# SenseBox-MCU-2-2.net
KiCad netlist of a schematic drawn in EAGLE
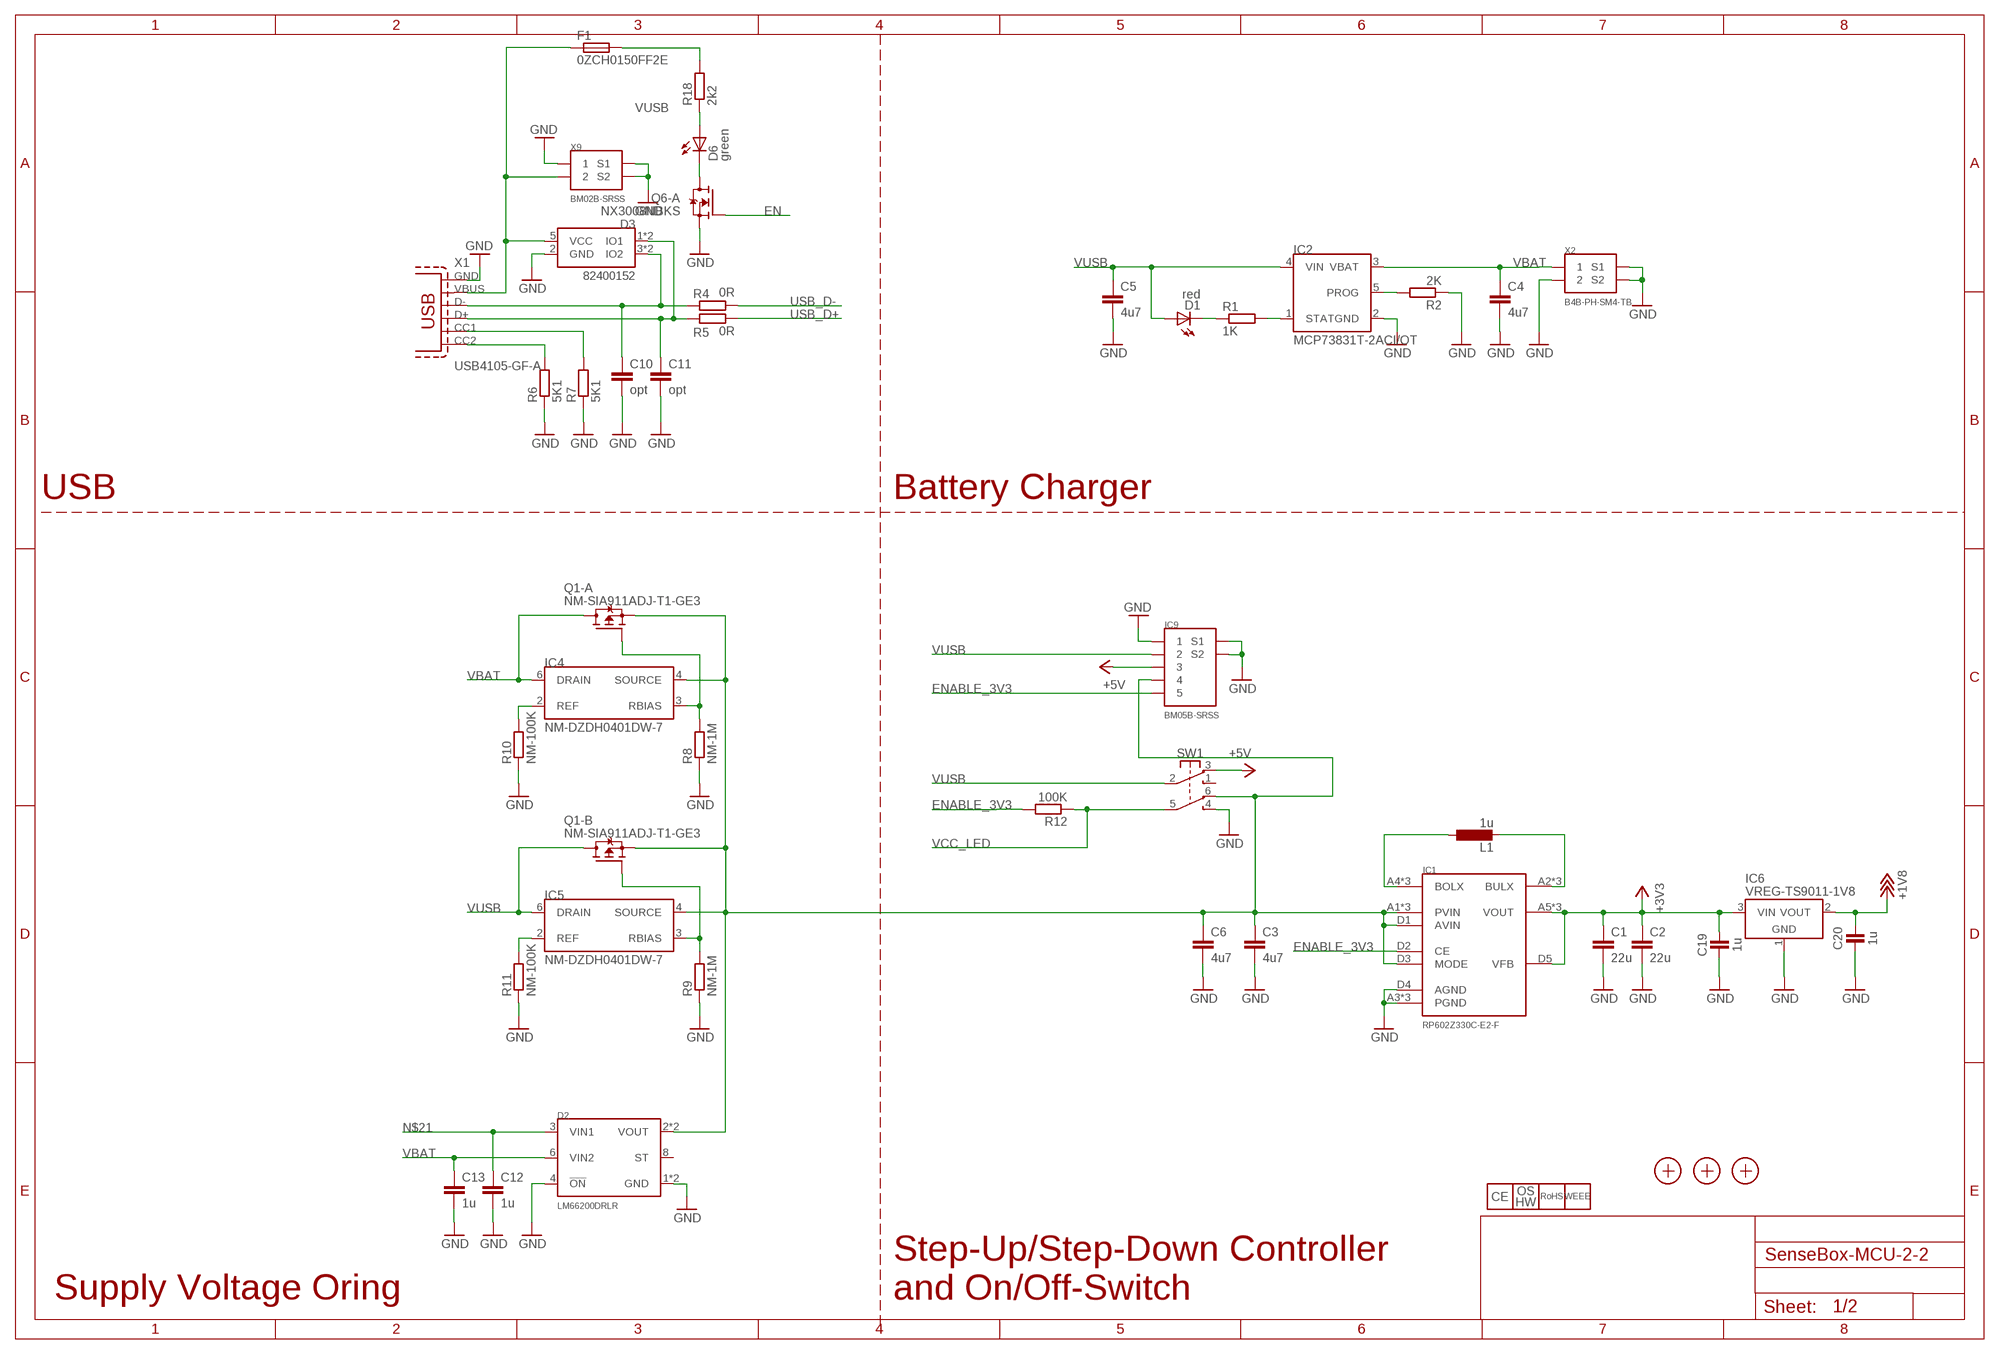
[diagram p0: schematic, sheet 1]
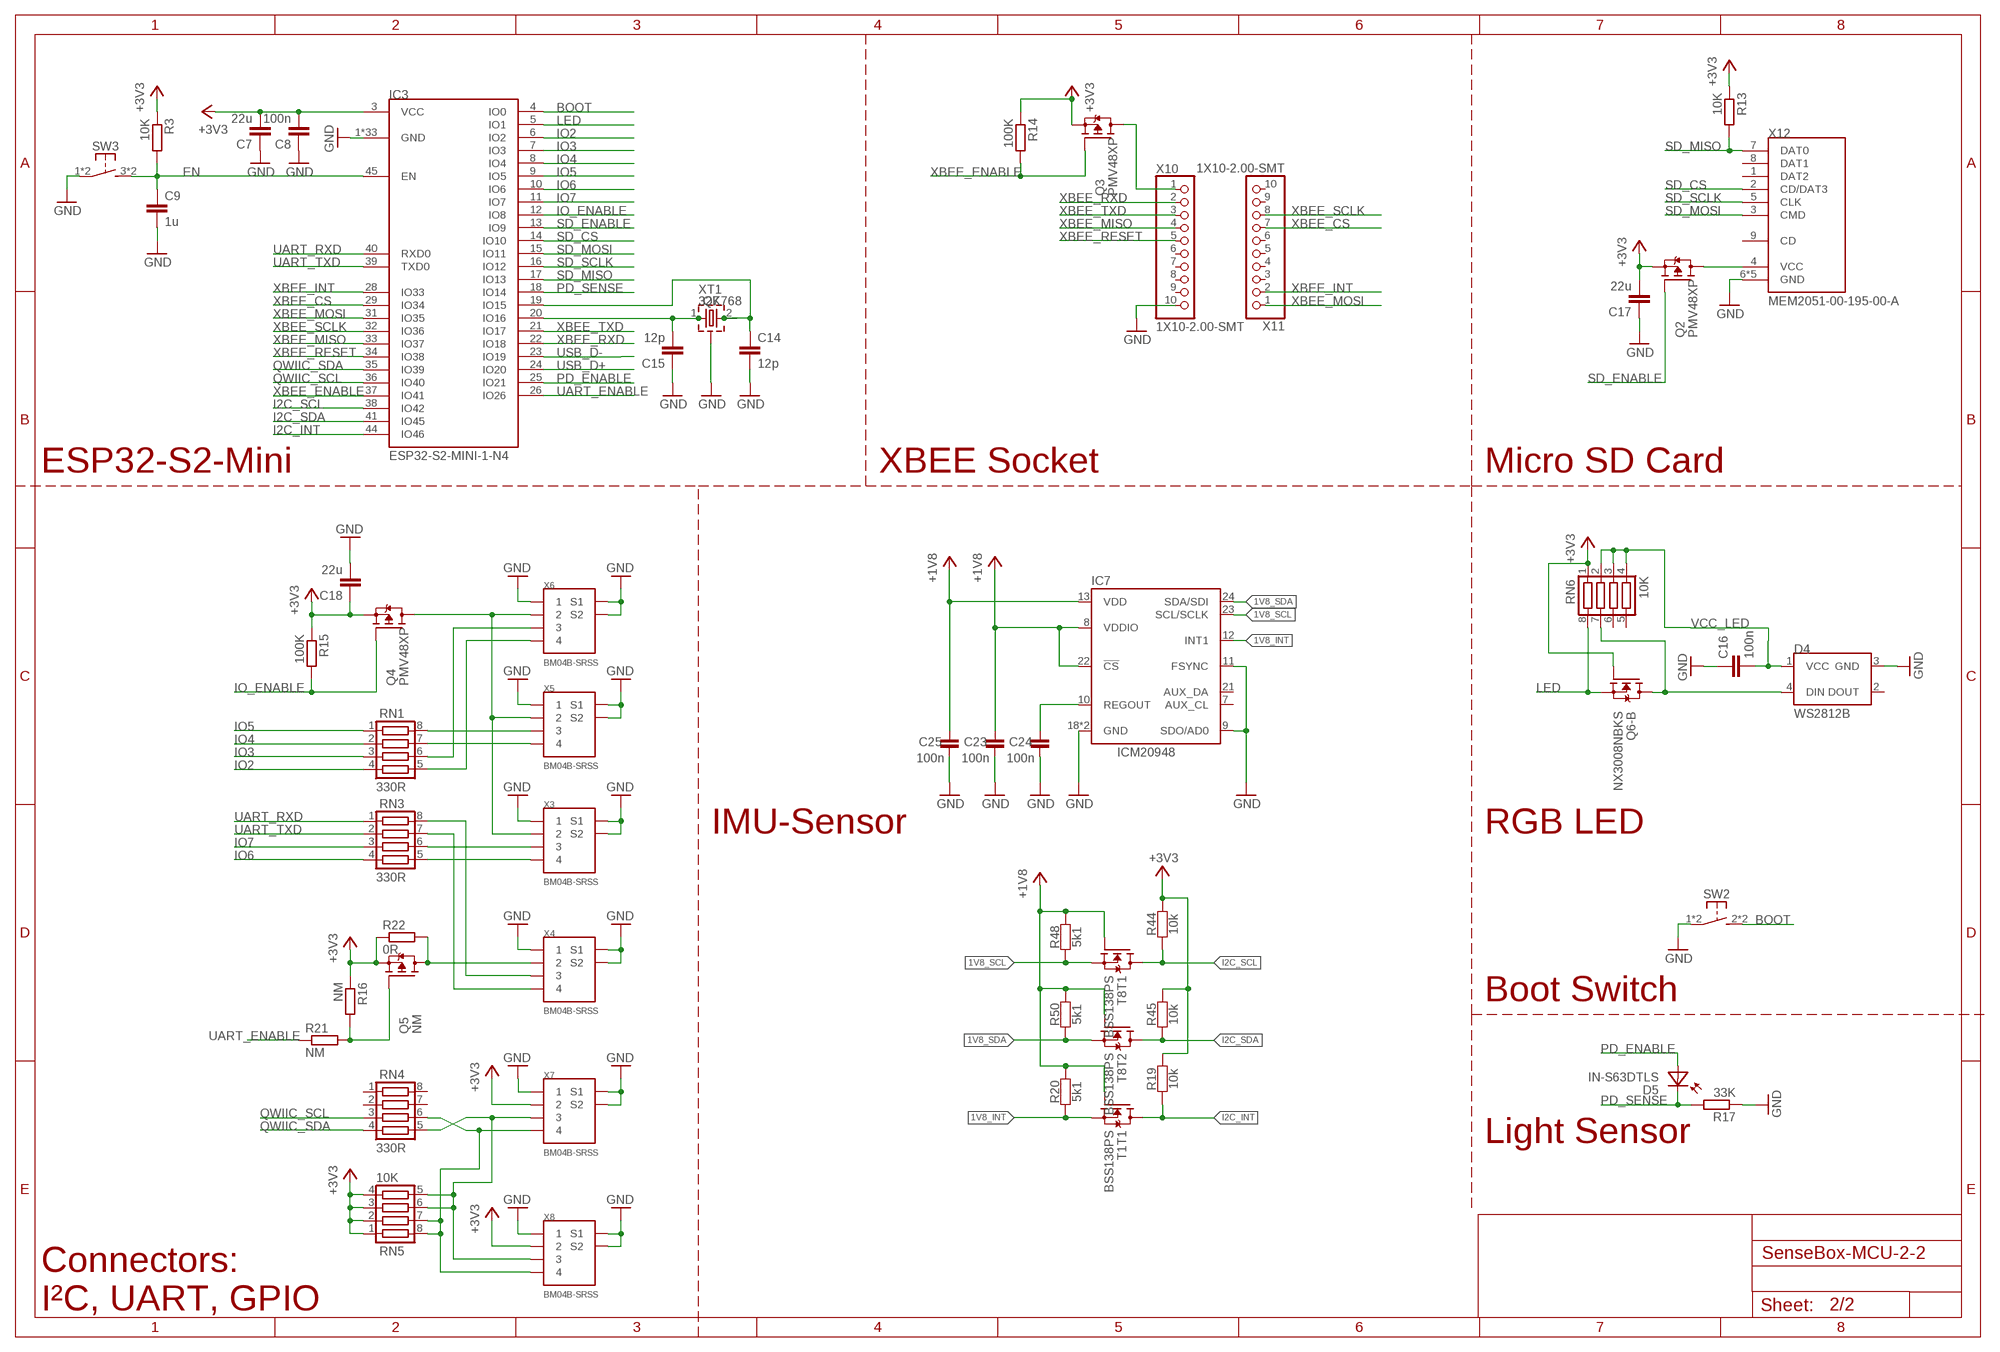
[diagram p1: schematic, sheet 2]

(export (version "E")
  (design (tool "Eeschema 10.0.6"))
  (components
    (comp (ref "C1")
      (value "22u")
      (footprint "eagle-import:0805N")
      (fields (field (name "VOLTAGE") "6V3"))
      (libsource (lib "eagle-import") (part "C_0805N_22U"))
    )
    (comp (ref "C2")
      (value "22u")
      (footprint "eagle-import:0805N")
      (fields (field (name "VOLTAGE") "6V3"))
      (libsource (lib "eagle-import") (part "C_0805N_22U"))
    )
    (comp (ref "C3")
      (value "4u7")
      (footprint "eagle-import:0603N")
      (fields (field (name "VOLTAGE") "6V3"))
      (libsource (lib "eagle-import") (part "C_0603N_4U7"))
    )
    (comp (ref "C4")
      (value "4u7")
      (footprint "eagle-import:0603N")
      (fields (field (name "VOLTAGE") "6V3"))
      (libsource (lib "eagle-import") (part "C_0603N_4U7"))
    )
    (comp (ref "C5")
      (value "4u7")
      (footprint "eagle-import:0603N")
      (fields (field (name "VOLTAGE") "6V3"))
      (libsource (lib "eagle-import") (part "C_0603N_4U7"))
    )
    (comp (ref "C6")
      (value "4u7")
      (footprint "eagle-import:0603N")
      (fields (field (name "VOLTAGE") "6V3"))
      (libsource (lib "eagle-import") (part "C_0603N_4U7"))
    )
    (comp (ref "C10")
      (value "opt")
      (footprint "eagle-import:0402N")
      (libsource (lib "eagle-import") (part "C_0402N"))
    )
    (comp (ref "C11")
      (value "opt")
      (footprint "eagle-import:0402N")
      (libsource (lib "eagle-import") (part "C_0402N"))
    )
    (comp (ref "C12")
      (value "1u")
      (footprint "eagle-import:0402N")
      (fields (field (name "VOLTAGE") "10"))
      (libsource (lib "eagle-import") (part "C_0402N_1U"))
    )
    (comp (ref "C13")
      (value "1u")
      (footprint "eagle-import:0402N")
      (fields (field (name "VOLTAGE") "10"))
      (libsource (lib "eagle-import") (part "C_0402N_1U"))
    )
    (comp (ref "C19")
      (value "1u")
      (footprint "eagle-import:C0402")
      (libsource (lib "eagle-import") (part "CAPACITOR-0402"))
    )
    (comp (ref "C20")
      (value "1u")
      (footprint "eagle-import:C0402")
      (libsource (lib "eagle-import") (part "CAPACITOR-0402"))
    )
    (comp (ref "D1")
      (value "red")
      (footprint "eagle-import:0603N")
      (libsource (lib "eagle-import") (part "LED_0603N_RED"))
    )
    (comp (ref "D2")
      (value "LM66200DRLR")
      (footprint "eagle-import:SOT-5X3")
      (libsource (lib "eagle-import") (part "LM66200"))
    )
    (comp (ref "D3")
      (value "82400152")
      (footprint "eagle-import:SOT563")
      (libsource (lib "eagle-import") (part "TVS-3-CHANNELS_SOT563_WE-TVS"))
    )
    (comp (ref "D6")
      (value "green")
      (footprint "eagle-import:0603N")
      (libsource (lib "eagle-import") (part "LED_0603N_GREEN"))
    )
    (comp (ref "F1")
      (value "0ZCH0150FF2E")
      (footprint "eagle-import:1210N")
      (libsource (lib "eagle-import") (part "FUSE-2PIN_1210N_1.5A"))
    )
    (comp (ref "IC1")
      (value "RP602Z330C-E2-F")
      (footprint "eagle-import:WLCSP-20-P1")
      (libsource (lib "eagle-import") (part "RP602_WLCSP-20-P1_RP602Z330C-E2-F"))
    )
    (comp (ref "IC2")
      (value "MCP73831T-2ACI/OT")
      (footprint "eagle-import:SOT23-5")
      (libsource (lib "eagle-import") (part "MCP73831_SOT23-5_MCP73831T-2ACI/OT"))
    )
    (comp (ref "IC4")
      (value "NM-DZDH0401DW-7")
      (footprint "eagle-import:SOT363")
      (libsource (lib "eagle-import") (part "DZDH0401DW"))
    )
    (comp (ref "IC5")
      (value "NM-DZDH0401DW-7")
      (footprint "eagle-import:SOT363")
      (libsource (lib "eagle-import") (part "DZDH0401DW"))
    )
    (comp (ref "IC6")
      (value "VREG-TS9011-1V8")
      (footprint "eagle-import:SOT23")
      (libsource (lib "eagle-import") (part "VREG-TS9011-1V8"))
    )
    (comp (ref "IC9")
      (value "BM05B-SRSS")
      (footprint "eagle-import:BM05B-SRSS")
      (libsource (lib "eagle-import") (part "SH-05_BM05B-SRSS_BM05B-SRSS"))
    )
    (comp (ref "L1")
      (value "1u")
      (footprint "eagle-import:5040")
      (libsource (lib "eagle-import") (part "L_5040_WE-LQS-1U"))
    )
    (comp (ref "LOGO1")
      (value "LOGO_CE-2")
      (footprint "eagle-import:CE_2MM")
      (libsource (lib "eagle-import") (part "LOGO_CE-2"))
    )
    (comp (ref "LOGO2")
      (value "LOGO_OSHW-2")
      (footprint "eagle-import:OSHW_2MM")
      (libsource (lib "eagle-import") (part "LOGO_OSHW-2"))
    )
    (comp (ref "LOGO3")
      (value "LOGO_ROHS-2")
      (footprint "eagle-import:ROHS_2MM")
      (libsource (lib "eagle-import") (part "LOGO_ROHS-2"))
    )
    (comp (ref "LOGO4")
      (value "LOGO_WEEE-4")
      (footprint "eagle-import:WEEE_4MM")
      (libsource (lib "eagle-import") (part "LOGO_WEEE-4"))
    )
    (comp (ref "Q1")
      (value "NM-SIA911ADJ-T1-GE3")
      (footprint "eagle-import:POWERPAK-SC70-6")
      (fields (field (name "VOLTAGE") "20"))
      (libsource (lib "eagle-import") (part "MOSFET-P-DUAL_POWERPAK-SC70-6_SIA911ADJ-T1-GE3"))
    )
    (comp (ref "Q6")
      (value "NX3008NBKS")
      (footprint "eagle-import:SOT363")
      (fields (field (name "POWER") "0.3") (field (name "VOLTAGE") "30"))
      (libsource (lib "eagle-import") (part "MOSFET-N-DUAL_SOT363_NX3008NBKS"))
    )
    (comp (ref "R1")
      (value "1K")
      (footprint "eagle-import:0402N")
      (fields (field (name "POWER") "0.063") (field (name "TOLERANCE") "1%") (field (name "VOLTAGE") "50"))
      (libsource (lib "eagle-import") (part "R_0402N_1K"))
    )
    (comp (ref "R2")
      (value "2K")
      (footprint "eagle-import:0402N")
      (fields (field (name "POWER") "0.063") (field (name "TOLERANCE") "1%") (field (name "VOLTAGE") "50"))
      (libsource (lib "eagle-import") (part "R_0402N_2K"))
    )
    (comp (ref "R4")
      (value "0R")
      (footprint "eagle-import:0402N")
      (libsource (lib "eagle-import") (part "R_0402N_0R"))
    )
    (comp (ref "R5")
      (value "0R")
      (footprint "eagle-import:0402N")
      (libsource (lib "eagle-import") (part "R_0402N_0R"))
    )
    (comp (ref "R6")
      (value "5K1")
      (footprint "eagle-import:0402N")
      (fields (field (name "POWER") "0.063") (field (name "TOLERANCE") "1%") (field (name "VOLTAGE") "50"))
      (libsource (lib "eagle-import") (part "R_0402N_5K1"))
    )
    (comp (ref "R7")
      (value "5K1")
      (footprint "eagle-import:0402N")
      (fields (field (name "POWER") "0.063") (field (name "TOLERANCE") "1%") (field (name "VOLTAGE") "50"))
      (libsource (lib "eagle-import") (part "R_0402N_5K1"))
    )
    (comp (ref "R8")
      (value "NM-1M")
      (footprint "eagle-import:0402N")
      (fields (field (name "POWER") "0.063") (field (name "TOLERANCE") "1%") (field (name "VOLTAGE") "50"))
      (libsource (lib "eagle-import") (part "R_0402N_1M"))
    )
    (comp (ref "R9")
      (value "NM-1M")
      (footprint "eagle-import:0402N")
      (fields (field (name "POWER") "0.063") (field (name "TOLERANCE") "1%") (field (name "VOLTAGE") "50"))
      (libsource (lib "eagle-import") (part "R_0402N_1M"))
    )
    (comp (ref "R10")
      (value "NM-100K")
      (footprint "eagle-import:0402N")
      (fields (field (name "POWER") "0.063") (field (name "TOLERANCE") "1%") (field (name "VOLTAGE") "50"))
      (libsource (lib "eagle-import") (part "R_0402N_100K"))
    )
    (comp (ref "R11")
      (value "NM-100K")
      (footprint "eagle-import:0402N")
      (fields (field (name "POWER") "0.063") (field (name "TOLERANCE") "1%") (field (name "VOLTAGE") "50"))
      (libsource (lib "eagle-import") (part "R_0402N_100K"))
    )
    (comp (ref "R12")
      (value "100K")
      (footprint "eagle-import:0402N")
      (fields (field (name "POWER") "0.063") (field (name "TOLERANCE") "1%") (field (name "VOLTAGE") "50"))
      (libsource (lib "eagle-import") (part "R_0402N_100K"))
    )
    (comp (ref "R18")
      (value "2k2")
      (footprint "eagle-import:0402N")
      (fields (field (name "POWER") "0.063") (field (name "TOLERANCE") "1%") (field (name "VOLTAGE") "50"))
      (libsource (lib "eagle-import") (part "R_0402N_1K"))
    )
    (comp (ref "SW1")
      (value "SW-2UM-CUS22B")
      (footprint "eagle-import:CUS22B")
      (libsource (lib "eagle-import") (part "SW-2UM-CUS22B"))
    )
    (comp (ref "X1")
      (value "USB4105-GF-A")
      (footprint "eagle-import:USB4105")
      (libsource (lib "eagle-import") (part "USB-C-2.0_USB4105_USB4105-GF-A"))
    )
    (comp (ref "X2")
      (value "B4B-PH-SM4-TB")
      (footprint "eagle-import:B4B-PH-SM4-TB")
      (libsource (lib "eagle-import") (part "SH-02_B4B-PH-SM4-TB_B4B-PH-SM4-TB"))
    )
    (comp (ref "X9")
      (value "BM02B-SRSS")
      (footprint "eagle-import:BM02B-SRSS")
      (libsource (lib "eagle-import") (part "SH-02_BM02B-SRSS_BM02B-SRSS"))
    )
    (comp (ref "X13")
      (value "PASSER-07")
      (footprint "eagle-import:PASSER_07MM")
      (libsource (lib "eagle-import") (part "PASSER-07"))
    )
    (comp (ref "X14")
      (value "PASSER-07")
      (footprint "eagle-import:PASSER_07MM")
      (libsource (lib "eagle-import") (part "PASSER-07"))
    )
    (comp (ref "X15")
      (value "PASSER-07")
      (footprint "eagle-import:PASSER_07MM")
      (libsource (lib "eagle-import") (part "PASSER-07"))
    )
    (comp (ref "C7")
      (value "22u")
      (footprint "eagle-import:0805N")
      (fields (field (name "VOLTAGE") "6V3"))
      (libsource (lib "eagle-import") (part "C_0805N_22U"))
    )
    (comp (ref "C8")
      (value "100n")
      (footprint "eagle-import:0402N")
      (fields (field (name "VOLTAGE") "16"))
      (libsource (lib "eagle-import") (part "C_0402N_100N"))
    )
    (comp (ref "C9")
      (value "1u")
      (footprint "eagle-import:0402N")
      (fields (field (name "VOLTAGE") "10"))
      (libsource (lib "eagle-import") (part "C_0402N_1U"))
    )
    (comp (ref "C14")
      (value "12p")
      (footprint "eagle-import:0402N")
      (fields (field (name "VOLTAGE") "50"))
      (libsource (lib "eagle-import") (part "C_0402N_12P"))
    )
    (comp (ref "C15")
      (value "12p")
      (footprint "eagle-import:0402N")
      (fields (field (name "VOLTAGE") "50"))
      (libsource (lib "eagle-import") (part "C_0402N_12P"))
    )
    (comp (ref "C16")
      (value "100n")
      (footprint "eagle-import:0402N")
      (fields (field (name "VOLTAGE") "16"))
      (libsource (lib "eagle-import") (part "C_0402N_100N"))
    )
    (comp (ref "C17")
      (value "22u")
      (footprint "eagle-import:0805N")
      (fields (field (name "VOLTAGE") "6V3"))
      (libsource (lib "eagle-import") (part "C_0805N_22U"))
    )
    (comp (ref "C18")
      (value "22u")
      (footprint "eagle-import:0805N")
      (fields (field (name "VOLTAGE") "6V3"))
      (libsource (lib "eagle-import") (part "C_0805N_22U"))
    )
    (comp (ref "C23")
      (value "100n")
      (footprint "eagle-import:C0402")
      (libsource (lib "eagle-import") (part "CAPACITOR-0402"))
    )
    (comp (ref "C24")
      (value "100n")
      (footprint "eagle-import:C0402")
      (libsource (lib "eagle-import") (part "CAPACITOR-0402"))
    )
    (comp (ref "C25")
      (value "100n")
      (footprint "eagle-import:C0402")
      (libsource (lib "eagle-import") (part "CAPACITOR-0402"))
    )
    (comp (ref "D4")
      (value "WS2812B")
      (footprint "eagle-import:5050")
      (libsource (lib "eagle-import") (part "LED-ADRESSABLE_5050_WS2812B"))
    )
    (comp (ref "D5")
      (value "IN-S63DTLS")
      (footprint "eagle-import:0603N")
      (libsource (lib "eagle-import") (part "PHOTODIODE_0603N_IN-S63DTLS"))
    )
    (comp (ref "IC3")
      (value "ESP32-S2-MINI-1-N4")
      (footprint "eagle-import:ESP32-S2-MINI")
      (libsource (lib "eagle-import") (part "ESP32-S2-MINI_ESP32-S2-MINI_ESP32-S2-MINI-1-N4"))
    )
    (comp (ref "IC7")
      (value "ICM20948")
      (footprint "eagle-import:QFN24-3X3")
      (libsource (lib "eagle-import") (part "ICM20948"))
    )
    (comp (ref "Q2")
      (value "PMV48XP")
      (footprint "eagle-import:SOT23")
      (fields (field (name "VOLTAGE") "20"))
      (libsource (lib "eagle-import") (part "MOSFET-P_SOT23'_PMV48XP"))
    )
    (comp (ref "Q3")
      (value "PMV48XP")
      (footprint "eagle-import:SOT23")
      (fields (field (name "VOLTAGE") "20"))
      (libsource (lib "eagle-import") (part "MOSFET-P_SOT23'_PMV48XP"))
    )
    (comp (ref "Q4")
      (value "PMV48XP")
      (footprint "eagle-import:SOT23")
      (fields (field (name "VOLTAGE") "20"))
      (libsource (lib "eagle-import") (part "MOSFET-P_SOT23'_PMV48XP"))
    )
    (comp (ref "Q5")
      (value "NM")
      (footprint "eagle-import:SOT23")
      (fields (field (name "VOLTAGE") "20"))
      (libsource (lib "eagle-import") (part "MOSFET-P_SOT23'_PMV48XP"))
    )
    (comp (ref "Q7")
      (value "CRYSTAL-ZM315")
      (footprint "eagle-import:CRYSTAL_ZM315")
      (libsource (lib "eagle-import") (part "CRYSTAL-ZM315"))
    )
    (comp (ref "R3")
      (value "10K")
      (footprint "eagle-import:0402N")
      (fields (field (name "POWER") "0.063") (field (name "TOLERANCE") "1%") (field (name "VOLTAGE") "50"))
      (libsource (lib "eagle-import") (part "R_0402N_10K"))
    )
    (comp (ref "R13")
      (value "10K")
      (footprint "eagle-import:0402N")
      (fields (field (name "POWER") "0.063") (field (name "TOLERANCE") "1%") (field (name "VOLTAGE") "50"))
      (libsource (lib "eagle-import") (part "R_0402N_10K"))
    )
    (comp (ref "R14")
      (value "100K")
      (footprint "eagle-import:0402N")
      (fields (field (name "POWER") "0.063") (field (name "TOLERANCE") "1%") (field (name "VOLTAGE") "50"))
      (libsource (lib "eagle-import") (part "R_0402N_100K"))
    )
    (comp (ref "R15")
      (value "100K")
      (footprint "eagle-import:0402N")
      (fields (field (name "POWER") "0.063") (field (name "TOLERANCE") "1%") (field (name "VOLTAGE") "50"))
      (libsource (lib "eagle-import") (part "R_0402N_100K"))
    )
    (comp (ref "R16")
      (value "NM")
      (footprint "eagle-import:0402N")
      (fields (field (name "POWER") "0.063") (field (name "TOLERANCE") "1%") (field (name "VOLTAGE") "50"))
      (libsource (lib "eagle-import") (part "R_0402N_100K"))
    )
    (comp (ref "R17")
      (value "33K")
      (footprint "eagle-import:0402N")
      (fields (field (name "POWER") "0.063") (field (name "TOLERANCE") "1%") (field (name "VOLTAGE") "50"))
      (libsource (lib "eagle-import") (part "R_0402N_33K"))
    )
    (comp (ref "R19")
      (value "10k")
      (footprint "eagle-import:C0402")
      (libsource (lib "eagle-import") (part "RESISTOR-0402"))
    )
    (comp (ref "R20")
      (value "5k1")
      (footprint "eagle-import:C0402")
      (libsource (lib "eagle-import") (part "RESISTOR-0402"))
    )
    (comp (ref "R21")
      (value "NM")
      (footprint "eagle-import:0402N")
      (fields (field (name "POWER") "0.063") (field (name "TOLERANCE") "1%") (field (name "VOLTAGE") "50"))
      (libsource (lib "eagle-import") (part "R_0402N_100K"))
    )
    (comp (ref "R22")
      (value "0R")
      (footprint "eagle-import:0402N")
      (fields (field (name "POWER") "0.063") (field (name "TOLERANCE") "1%") (field (name "VOLTAGE") "50"))
      (libsource (lib "eagle-import") (part "R_0402N_100K"))
    )
    (comp (ref "R44")
      (value "10k")
      (footprint "eagle-import:C0402")
      (libsource (lib "eagle-import") (part "RESISTOR-0402"))
    )
    (comp (ref "R45")
      (value "10k")
      (footprint "eagle-import:C0402")
      (libsource (lib "eagle-import") (part "RESISTOR-0402"))
    )
    (comp (ref "R48")
      (value "5k1")
      (footprint "eagle-import:C0402")
      (libsource (lib "eagle-import") (part "RESISTOR-0402"))
    )
    (comp (ref "R50")
      (value "5k1")
      (footprint "eagle-import:C0402")
      (libsource (lib "eagle-import") (part "RESISTOR-0402"))
    )
    (comp (ref "RN1")
      (value "330R")
      (footprint "eagle-import:CAY16")
      (fields (field (name "POWER") "0.062") (field (name "TOLERANCE") "5%") (field (name "VOLTAGE") "50"))
      (libsource (lib "eagle-import") (part "RN4_CAY16_330R"))
    )
    (comp (ref "RN3")
      (value "330R")
      (footprint "eagle-import:CAY16")
      (fields (field (name "POWER") "0.062") (field (name "TOLERANCE") "5%") (field (name "VOLTAGE") "50"))
      (libsource (lib "eagle-import") (part "RN4_CAY16_330R"))
    )
    (comp (ref "RN4")
      (value "330R")
      (footprint "eagle-import:CAY16")
      (fields (field (name "POWER") "0.062") (field (name "TOLERANCE") "5%") (field (name "VOLTAGE") "50"))
      (libsource (lib "eagle-import") (part "RN4_CAY16_330R"))
    )
    (comp (ref "RN5")
      (value "10K")
      (footprint "eagle-import:CAY16")
      (fields (field (name "POWER") "0.062") (field (name "TOLERANCE") "5%") (field (name "VOLTAGE") "50"))
      (libsource (lib "eagle-import") (part "RN4_CAY16_10K"))
    )
    (comp (ref "RN6")
      (value "10K")
      (footprint "eagle-import:CAY16")
      (fields (field (name "POWER") "0.062") (field (name "TOLERANCE") "5%") (field (name "VOLTAGE") "50"))
      (libsource (lib "eagle-import") (part "RN4_CAY16_10K"))
    )
    (comp (ref "SW2")
      (value "SW-TACTILE-TL3365")
      (footprint "eagle-import:TL3365")
      (libsource (lib "eagle-import") (part "SW-TACTILE-TL3365"))
    )
    (comp (ref "SW3")
      (value "SW-TACTILE-PTS840P")
      (footprint "eagle-import:PTS840P")
      (libsource (lib "eagle-import") (part "SW-TACTILE-PTS840P"))
    )
    (comp (ref "T1")
      (value "BSS138PS")
      (footprint "eagle-import:SOT363")
      (libsource (lib "eagle-import") (part "BSS138PS"))
    )
    (comp (ref "T8")
      (value "BSS138PS")
      (footprint "eagle-import:SOT363")
      (libsource (lib "eagle-import") (part "BSS138PS"))
    )
    (comp (ref "X3")
      (value "BM04B-SRSS")
      (footprint "eagle-import:BM04B-SRSS")
      (libsource (lib "eagle-import") (part "SH-04_BM04B-SRSS_BM04B-SRSS"))
    )
    (comp (ref "X4")
      (value "BM04B-SRSS")
      (footprint "eagle-import:BM04B-SRSS")
      (libsource (lib "eagle-import") (part "SH-04_BM04B-SRSS_BM04B-SRSS"))
    )
    (comp (ref "X5")
      (value "BM04B-SRSS")
      (footprint "eagle-import:BM04B-SRSS")
      (libsource (lib "eagle-import") (part "SH-04_BM04B-SRSS_BM04B-SRSS"))
    )
    (comp (ref "X6")
      (value "BM04B-SRSS")
      (footprint "eagle-import:BM04B-SRSS")
      (libsource (lib "eagle-import") (part "SH-04_BM04B-SRSS_BM04B-SRSS"))
    )
    (comp (ref "X7")
      (value "BM04B-SRSS")
      (footprint "eagle-import:BM04B-SRSS")
      (libsource (lib "eagle-import") (part "SH-04_BM04B-SRSS_BM04B-SRSS"))
    )
    (comp (ref "X8")
      (value "BM04B-SRSS")
      (footprint "eagle-import:BM04B-SRSS")
      (libsource (lib "eagle-import") (part "SH-04_BM04B-SRSS_BM04B-SRSS"))
    )
    (comp (ref "X10")
      (value "1X10-2.00-SMT")
      (footprint "eagle-import:1X10-2.00-SMD")
      (libsource (lib "eagle-import") (part "1X10_2.00-SMT"))
    )
    (comp (ref "X11")
      (value "1X10-2.00-SMT")
      (footprint "eagle-import:1X10-2.00-SMD")
      (libsource (lib "eagle-import") (part "1X10_2.00-SMT"))
    )
    (comp (ref "X12")
      (value "MEM2051-00-195-00-A")
      (footprint "eagle-import:MEM2051")
      (libsource (lib "eagle-import") (part "SD-CARD2_MEM2051"))
    )
    (comp (ref "XT1")
      (value "32K768")
      (footprint "eagle-import:1.4X1.5X5.2")
      (libsource (lib "eagle-import") (part "CRYSTAL-1GND_1.4X1.5X5.2"))
    )
  )
  (nets
    (net (code "1") (name "+1V8") (class "Default")
      (node (ref "C20") (pin "2") (pinfunction "2_2") (pintype "passive"))
      (node (ref "C23") (pin "2") (pinfunction "2_2") (pintype "passive"))
      (node (ref "C25") (pin "2") (pinfunction "2_2") (pintype "passive"))
      (node (ref "IC6") (pin "2") (pinfunction "VOUT_2") (pintype "power_in"))
      (node (ref "IC7") (pin "13") (pinfunction "VDD_13") (pintype "power_in"))
      (node (ref "IC7") (pin "22") (pinfunction "~{CS}_22") (pintype "bidirectional"))
      (node (ref "IC7") (pin "8") (pinfunction "VDDIO_8") (pintype "power_in"))
      (node (ref "R20") (pin "2") (pinfunction "2_2") (pintype "passive"))
      (node (ref "R48") (pin "2") (pinfunction "2_2") (pintype "passive"))
      (node (ref "R50") (pin "2") (pinfunction "2_2") (pintype "passive"))
      (node (ref "T1") (pin "2") (pinfunction "G_2") (pintype "passive"))
      (node (ref "T8") (pin "2") (pinfunction "G_2") (pintype "passive"))
      (node (ref "T8") (pin "5") (pinfunction "G_5") (pintype "passive"))
    )
    (net (code "2") (name "+3V3") (class "Default")
      (node (ref "C1") (pin "1") (pinfunction "1_1") (pintype "passive"))
      (node (ref "C17") (pin "2") (pinfunction "2_2") (pintype "passive"))
      (node (ref "C18") (pin "1") (pinfunction "1_1") (pintype "passive"))
      (node (ref "C19") (pin "2") (pinfunction "2_2") (pintype "passive"))
      (node (ref "C2") (pin "1") (pinfunction "1_1") (pintype "passive"))
      (node (ref "C7") (pin "2") (pinfunction "2_2") (pintype "passive"))
      (node (ref "C8") (pin "2") (pinfunction "2_2") (pintype "passive"))
      (node (ref "IC1") (pin "A5") (pinfunction "VOUT_A5") (pintype "power_in"))
      (node (ref "IC1") (pin "B5") (pinfunction "VOUT_B5") (pintype "power_in"))
      (node (ref "IC1") (pin "C5") (pinfunction "VOUT_C5") (pintype "power_in"))
      (node (ref "IC1") (pin "D5") (pinfunction "VFB_D5") (pintype "input"))
      (node (ref "IC3") (pin "3") (pinfunction "VCC_3") (pintype "power_in"))
      (node (ref "IC6") (pin "3") (pinfunction "VIN_3") (pintype "power_in"))
      (node (ref "Q2") (pin "2") (pinfunction "S_2") (pintype "passive"))
      (node (ref "Q3") (pin "2") (pinfunction "S_2") (pintype "passive"))
      (node (ref "Q4") (pin "2") (pinfunction "S_2") (pintype "passive"))
      (node (ref "Q5") (pin "2") (pinfunction "S_2") (pintype "passive"))
      (node (ref "Q6") (pin "5") (pinfunction "G_5") (pintype "passive"))
      (node (ref "R13") (pin "1") (pinfunction "1_1") (pintype "passive"))
      (node (ref "R14") (pin "1") (pinfunction "1_1") (pintype "passive"))
      (node (ref "R15") (pin "1") (pinfunction "1_1") (pintype "passive"))
      (node (ref "R16") (pin "1") (pinfunction "1_1") (pintype "passive"))
      (node (ref "R19") (pin "2") (pinfunction "2_2") (pintype "passive"))
      (node (ref "R22") (pin "1") (pinfunction "1_1") (pintype "passive"))
      (node (ref "R3") (pin "1") (pinfunction "1_1") (pintype "passive"))
      (node (ref "R44") (pin "2") (pinfunction "2_2") (pintype "passive"))
      (node (ref "R45") (pin "2") (pinfunction "2_2") (pintype "passive"))
      (node (ref "RN5") (pin "1") (pinfunction "1_1") (pintype "passive"))
      (node (ref "RN5") (pin "2") (pinfunction "2_2") (pintype "passive"))
      (node (ref "RN5") (pin "3") (pinfunction "3_3") (pintype "passive"))
      (node (ref "RN5") (pin "4") (pinfunction "4_4") (pintype "passive"))
      (node (ref "RN6") (pin "1") (pinfunction "1_1") (pintype "passive"))
      (node (ref "X7") (pin "2") (pinfunction "2_2") (pintype "bidirectional"))
      (node (ref "X8") (pin "2") (pinfunction "2_2") (pintype "bidirectional"))
    )
    (net (code "3") (name "+5V") (class "Default")
      (node (ref "IC9") (pin "3") (pinfunction "3_3") (pintype "bidirectional"))
      (node (ref "SW1") (pin "3") (pinfunction "NC1_3") (pintype "passive"))
    )
    (net (code "4") (name "1V8_INT") (class "Default")
      (node (ref "IC7") (pin "12") (pinfunction "INT1_12") (pintype "output"))
      (node (ref "R20") (pin "1") (pinfunction "1_1") (pintype "passive"))
      (node (ref "T1") (pin "1") (pinfunction "S_1") (pintype "passive"))
    )
    (net (code "5") (name "1V8_SCL") (class "Default")
      (node (ref "IC7") (pin "23") (pinfunction "SCL/SCLK_23") (pintype "bidirectional"))
      (node (ref "R48") (pin "1") (pinfunction "1_1") (pintype "passive"))
      (node (ref "T8") (pin "1") (pinfunction "S_1") (pintype "passive"))
    )
    (net (code "6") (name "1V8_SDA") (class "Default")
      (node (ref "IC7") (pin "24") (pinfunction "SDA/SDI_24") (pintype "bidirectional"))
      (node (ref "R50") (pin "1") (pinfunction "1_1") (pintype "passive"))
      (node (ref "T8") (pin "4") (pinfunction "S_4") (pintype "passive"))
    )
    (net (code "7") (name "BOOT") (class "Default")
      (node (ref "IC3") (pin "4") (pinfunction "IO0_4") (pintype "bidirectional"))
      (node (ref "SW2") (pin "2") (pinfunction "S1_2") (pintype "passive"))
      (node (ref "SW2") (pin "3") (pinfunction "S1_3") (pintype "passive"))
    )
    (net (code "8") (name "EN") (class "Default")
      (node (ref "C9") (pin "1") (pinfunction "1_1") (pintype "passive"))
      (node (ref "IC3") (pin "45") (pinfunction "EN_45") (pintype "input"))
      (node (ref "Q6") (pin "2") (pinfunction "G_2") (pintype "passive"))
      (node (ref "R3") (pin "2") (pinfunction "2_2") (pintype "passive"))
      (node (ref "SW3") (pin "3") (pinfunction "S1_3") (pintype "passive"))
      (node (ref "SW3") (pin "4") (pinfunction "S1_4") (pintype "passive"))
    )
    (net (code "9") (name "ENABLE_3V3") (class "Default")
      (node (ref "IC1") (pin "D2") (pinfunction "CE_D2") (pintype "input"))
      (node (ref "IC9") (pin "5") (pinfunction "5_5") (pintype "bidirectional"))
      (node (ref "R12") (pin "2") (pinfunction "2_2") (pintype "passive"))
    )
    (net (code "10") (name "GND") (class "Default")
      (node (ref "C1") (pin "2") (pinfunction "2_2") (pintype "passive"))
      (node (ref "C10") (pin "2") (pinfunction "2_2") (pintype "passive"))
      (node (ref "C11") (pin "2") (pinfunction "2_2") (pintype "passive"))
      (node (ref "C12") (pin "2") (pinfunction "2_2") (pintype "passive"))
      (node (ref "C13") (pin "2") (pinfunction "2_2") (pintype "passive"))
      (node (ref "C14") (pin "2") (pinfunction "2_2") (pintype "passive"))
      (node (ref "C15") (pin "1") (pinfunction "1_1") (pintype "passive"))
      (node (ref "C16") (pin "1") (pinfunction "1_1") (pintype "passive"))
      (node (ref "C17") (pin "1") (pinfunction "1_1") (pintype "passive"))
      (node (ref "C18") (pin "2") (pinfunction "2_2") (pintype "passive"))
      (node (ref "C19") (pin "1") (pinfunction "1_1") (pintype "passive"))
      (node (ref "C2") (pin "2") (pinfunction "2_2") (pintype "passive"))
      (node (ref "C20") (pin "1") (pinfunction "1_1") (pintype "passive"))
      (node (ref "C23") (pin "1") (pinfunction "1_1") (pintype "passive"))
      (node (ref "C24") (pin "1") (pinfunction "1_1") (pintype "passive"))
      (node (ref "C25") (pin "1") (pinfunction "1_1") (pintype "passive"))
      (node (ref "C3") (pin "2") (pinfunction "2_2") (pintype "passive"))
      (node (ref "C4") (pin "2") (pinfunction "2_2") (pintype "passive"))
      (node (ref "C5") (pin "2") (pinfunction "2_2") (pintype "passive"))
      (node (ref "C6") (pin "2") (pinfunction "2_2") (pintype "passive"))
      (node (ref "C7") (pin "1") (pinfunction "1_1") (pintype "passive"))
      (node (ref "C8") (pin "1") (pinfunction "1_1") (pintype "passive"))
      (node (ref "C9") (pin "2") (pinfunction "2_2") (pintype "passive"))
      (node (ref "D2") (pin "1") (pinfunction "GND_1") (pintype "power_in"))
      (node (ref "D2") (pin "4") (pinfunction "~{ON}_4") (pintype "input"))
      (node (ref "D2") (pin "5") (pinfunction "GND_5") (pintype "power_in"))
      (node (ref "D3") (pin "2") (pinfunction "GND_2") (pintype "power_in"))
      (node (ref "D4") (pin "3") (pinfunction "GND_3") (pintype "power_in"))
      (node (ref "IC1") (pin "A3") (pinfunction "PGND_A3") (pintype "power_in"))
      (node (ref "IC1") (pin "B3") (pinfunction "PGND_B3") (pintype "power_in"))
      (node (ref "IC1") (pin "C3") (pinfunction "PGND_C3") (pintype "power_in"))
      (node (ref "IC1") (pin "D4") (pinfunction "AGND_D4") (pintype "power_in"))
      (node (ref "IC2") (pin "2") (pinfunction "GND_2") (pintype "power_in"))
      (node (ref "IC3") (pin "1") (pinfunction "GND_1") (pintype "power_in"))
      (node (ref "IC3") (pin "2") (pinfunction "GND_2") (pintype "power_in"))
      (node (ref "IC3") (pin "30") (pinfunction "GND_30") (pintype "power_in"))
      (node (ref "IC3") (pin "42") (pinfunction "GND_42") (pintype "power_in"))
      (node (ref "IC3") (pin "43") (pinfunction "GND_43") (pintype "power_in"))
      (node (ref "IC3") (pin "46") (pinfunction "GND_46") (pintype "power_in"))
      (node (ref "IC3") (pin "47") (pinfunction "GND_47") (pintype "power_in"))
      (node (ref "IC3") (pin "48") (pinfunction "GND_48") (pintype "power_in"))
      (node (ref "IC3") (pin "49") (pinfunction "GND_49") (pintype "power_in"))
      (node (ref "IC3") (pin "50") (pinfunction "GND_50") (pintype "power_in"))
      (node (ref "IC3") (pin "51") (pinfunction "GND_51") (pintype "power_in"))
      (node (ref "IC3") (pin "52") (pinfunction "GND_52") (pintype "power_in"))
      (node (ref "IC3") (pin "53") (pinfunction "GND_53") (pintype "power_in"))
      (node (ref "IC3") (pin "54") (pinfunction "GND_54") (pintype "power_in"))
      (node (ref "IC3") (pin "55") (pinfunction "GND_55") (pintype "power_in"))
      (node (ref "IC3") (pin "56") (pinfunction "GND_56") (pintype "power_in"))
      (node (ref "IC3") (pin "57") (pinfunction "GND_57") (pintype "power_in"))
      (node (ref "IC3") (pin "58") (pinfunction "GND_58") (pintype "power_in"))
      (node (ref "IC3") (pin "59") (pinfunction "GND_59") (pintype "power_in"))
      (node (ref "IC3") (pin "60") (pinfunction "GND_60") (pintype "power_in"))
      (node (ref "IC3") (pin "61") (pinfunction "GND_61") (pintype "power_in"))
      (node (ref "IC3") (pin "62") (pinfunction "GND_62") (pintype "power_in"))
      (node (ref "IC3") (pin "63") (pinfunction "GND_63") (pintype "power_in"))
      (node (ref "IC3") (pin "64") (pinfunction "GND_64") (pintype "power_in"))
      (node (ref "IC3") (pin "65") (pinfunction "GND_65") (pintype "power_in"))
      (node (ref "IC3") (pin "66") (pinfunction "GND_66") (pintype "power_in"))
      (node (ref "IC3") (pin "67") (pinfunction "GND_67") (pintype "power_in"))
      (node (ref "IC3") (pin "68") (pinfunction "GND_68") (pintype "power_in"))
      (node (ref "IC3") (pin "69") (pinfunction "GND_69") (pintype "power_in"))
      (node (ref "IC3") (pin "70") (pinfunction "GND_70") (pintype "power_in"))
      (node (ref "IC3") (pin "71") (pinfunction "GND_71") (pintype "power_in"))
      (node (ref "IC3") (pin "72") (pinfunction "GND_72") (pintype "power_in"))
      (node (ref "IC3") (pin "73") (pinfunction "GND_73") (pintype "power_in"))
      (node (ref "IC6") (pin "1") (pinfunction "GND_1") (pintype "power_in"))
      (node (ref "IC7") (pin "11") (pinfunction "FSYNC_11") (pintype "input"))
      (node (ref "IC7") (pin "18") (pinfunction "GND_18") (pintype "power_in"))
      (node (ref "IC7") (pin "20") (pinfunction "GND_20") (pintype "power_in"))
      (node (ref "IC7") (pin "9") (pinfunction "SDO/AD0_9") (pintype "input"))
      (node (ref "IC9") (pin "1") (pinfunction "1_1") (pintype "bidirectional"))
      (node (ref "IC9") (pin "S1") (pinfunction "S1_S1") (pintype "bidirectional"))
      (node (ref "IC9") (pin "S2") (pinfunction "S2_S2") (pintype "bidirectional"))
      (node (ref "Q6") (pin "1") (pinfunction "S_1") (pintype "passive"))
      (node (ref "R10") (pin "1") (pinfunction "1_1") (pintype "passive"))
      (node (ref "R11") (pin "1") (pinfunction "1_1") (pintype "passive"))
      (node (ref "R17") (pin "1") (pinfunction "1_1") (pintype "passive"))
      (node (ref "R2") (pin "1") (pinfunction "1_1") (pintype "passive"))
      (node (ref "R6") (pin "1") (pinfunction "1_1") (pintype "passive"))
      (node (ref "R7") (pin "1") (pinfunction "1_1") (pintype "passive"))
      (node (ref "R8") (pin "1") (pinfunction "1_1") (pintype "passive"))
      (node (ref "R9") (pin "1") (pinfunction "1_1") (pintype "passive"))
      (node (ref "SW1") (pin "4") (pinfunction "NO2_4") (pintype "passive"))
      (node (ref "SW2") (pin "1") (pinfunction "P1_1") (pintype "passive"))
      (node (ref "SW2") (pin "4") (pinfunction "P1_4") (pintype "passive"))
      (node (ref "SW3") (pin "1") (pinfunction "P1_1") (pintype "passive"))
      (node (ref "SW3") (pin "2") (pinfunction "P1_2") (pintype "passive"))
      (node (ref "X1") (pin "A1_B12") (pinfunction "GND_A1_B12") (pintype "power_in"))
      (node (ref "X1") (pin "B1_A12") (pinfunction "GND_B1_A12") (pintype "power_in"))
      (node (ref "X1") (pin "S1") (pinfunction "GND_S1") (pintype "power_in"))
      (node (ref "X1") (pin "S2") (pinfunction "GND_S2") (pintype "power_in"))
      (node (ref "X1") (pin "S3") (pinfunction "GND_S3") (pintype "power_in"))
      (node (ref "X1") (pin "S4") (pinfunction "GND_S4") (pintype "power_in"))
      (node (ref "X10") (pin "10") (pinfunction "10_10") (pintype "passive"))
      (node (ref "X12") (pin "6") (pinfunction "GND_6") (pintype "power_in"))
      (node (ref "X12") (pin "S1") (pinfunction "GND_S1") (pintype "power_in"))
      (node (ref "X12") (pin "S2") (pinfunction "GND_S2") (pintype "power_in"))
      (node (ref "X12") (pin "S3") (pinfunction "GND_S3") (pintype "power_in"))
      (node (ref "X12") (pin "S4") (pinfunction "GND_S4") (pintype "power_in"))
      (node (ref "X2") (pin "2") (pinfunction "2_2") (pintype "bidirectional"))
      (node (ref "X2") (pin "SH1") (pinfunction "S1_SH1") (pintype "bidirectional"))
      (node (ref "X2") (pin "SH2") (pinfunction "S2_SH2") (pintype "bidirectional"))
      (node (ref "X3") (pin "1") (pinfunction "1_1") (pintype "bidirectional"))
      (node (ref "X3") (pin "S1") (pinfunction "S1_S1") (pintype "bidirectional"))
      (node (ref "X3") (pin "S2") (pinfunction "S2_S2") (pintype "bidirectional"))
      (node (ref "X4") (pin "1") (pinfunction "1_1") (pintype "bidirectional"))
      (node (ref "X4") (pin "S1") (pinfunction "S1_S1") (pintype "bidirectional"))
      (node (ref "X4") (pin "S2") (pinfunction "S2_S2") (pintype "bidirectional"))
      (node (ref "X5") (pin "1") (pinfunction "1_1") (pintype "bidirectional"))
      (node (ref "X5") (pin "S1") (pinfunction "S1_S1") (pintype "bidirectional"))
      (node (ref "X5") (pin "S2") (pinfunction "S2_S2") (pintype "bidirectional"))
      (node (ref "X6") (pin "1") (pinfunction "1_1") (pintype "bidirectional"))
      (node (ref "X6") (pin "S1") (pinfunction "S1_S1") (pintype "bidirectional"))
      (node (ref "X6") (pin "S2") (pinfunction "S2_S2") (pintype "bidirectional"))
      (node (ref "X7") (pin "1") (pinfunction "1_1") (pintype "bidirectional"))
      (node (ref "X7") (pin "S1") (pinfunction "S1_S1") (pintype "bidirectional"))
      (node (ref "X7") (pin "S2") (pinfunction "S2_S2") (pintype "bidirectional"))
      (node (ref "X8") (pin "1") (pinfunction "1_1") (pintype "bidirectional"))
      (node (ref "X8") (pin "S1") (pinfunction "S1_S1") (pintype "bidirectional"))
      (node (ref "X8") (pin "S2") (pinfunction "S2_S2") (pintype "bidirectional"))
      (node (ref "X9") (pin "1") (pinfunction "1_1") (pintype "bidirectional"))
      (node (ref "X9") (pin "S1") (pinfunction "S1_S1") (pintype "bidirectional"))
      (node (ref "X9") (pin "S2") (pinfunction "S2_S2") (pintype "bidirectional"))
      (node (ref "XT1") (pin "3") (pinfunction "GND_3") (pintype "power_in"))
    )
    (net (code "11") (name "I2C_INT") (class "Default")
      (node (ref "IC3") (pin "44") (pinfunction "IO46_44") (pintype "input"))
      (node (ref "R19") (pin "1") (pinfunction "1_1") (pintype "passive"))
      (node (ref "T1") (pin "6") (pinfunction "D_6") (pintype "passive"))
    )
    (net (code "12") (name "I2C_SCL") (class "Default")
      (node (ref "IC3") (pin "38") (pinfunction "IO42_38") (pintype "bidirectional"))
      (node (ref "R44") (pin "1") (pinfunction "1_1") (pintype "passive"))
      (node (ref "T8") (pin "6") (pinfunction "D_6") (pintype "passive"))
    )
    (net (code "13") (name "I2C_SDA") (class "Default")
      (node (ref "IC3") (pin "41") (pinfunction "IO45_41") (pintype "bidirectional"))
      (node (ref "R45") (pin "1") (pinfunction "1_1") (pintype "passive"))
      (node (ref "T8") (pin "3") (pinfunction "D_3") (pintype "passive"))
    )
    (net (code "14") (name "IO2") (class "Default")
      (node (ref "IC3") (pin "6") (pinfunction "IO2_6") (pintype "bidirectional"))
      (node (ref "RN1") (pin "4") (pinfunction "4_4") (pintype "passive"))
    )
    (net (code "15") (name "IO3") (class "Default")
      (node (ref "IC3") (pin "7") (pinfunction "IO3_7") (pintype "bidirectional"))
      (node (ref "RN1") (pin "3") (pinfunction "3_3") (pintype "passive"))
    )
    (net (code "16") (name "IO4") (class "Default")
      (node (ref "IC3") (pin "8") (pinfunction "IO4_8") (pintype "bidirectional"))
      (node (ref "RN1") (pin "2") (pinfunction "2_2") (pintype "passive"))
    )
    (net (code "17") (name "IO5") (class "Default")
      (node (ref "IC3") (pin "9") (pinfunction "IO5_9") (pintype "bidirectional"))
      (node (ref "RN1") (pin "1") (pinfunction "1_1") (pintype "passive"))
    )
    (net (code "18") (name "IO6") (class "Default")
      (node (ref "IC3") (pin "10") (pinfunction "IO6_10") (pintype "bidirectional"))
      (node (ref "RN3") (pin "4") (pinfunction "4_4") (pintype "passive"))
    )
    (net (code "19") (name "IO7") (class "Default")
      (node (ref "IC3") (pin "11") (pinfunction "IO7_11") (pintype "bidirectional"))
      (node (ref "RN3") (pin "3") (pinfunction "3_3") (pintype "passive"))
    )
    (net (code "20") (name "IO_ENABLE") (class "Default")
      (node (ref "IC3") (pin "12") (pinfunction "IO8_12") (pintype "bidirectional"))
      (node (ref "Q4") (pin "1") (pinfunction "G_1") (pintype "passive"))
      (node (ref "R15") (pin "2") (pinfunction "2_2") (pintype "passive"))
    )
    (net (code "21") (name "LED") (class "Default")
      (node (ref "IC3") (pin "5") (pinfunction "IO1_5") (pintype "bidirectional"))
      (node (ref "Q6") (pin "4") (pinfunction "S_4") (pintype "passive"))
      (node (ref "RN6") (pin "8") (pinfunction "8_8") (pintype "passive"))
    )
    (net (code "22") (name "N$21") (class "Default")
      (node (ref "C12") (pin "1") (pinfunction "1_1") (pintype "passive"))
      (node (ref "D2") (pin "3") (pinfunction "VIN1_3") (pintype "power_in"))
    )
    (net (code "23") (name "Net-(C10-Pad1)") (class "Default")
      (node (ref "C10") (pin "1") (pinfunction "1_1") (pintype "passive"))
      (node (ref "D3") (pin "3") (pinfunction "IO2_3") (pintype "passive"))
      (node (ref "D3") (pin "4") (pinfunction "IO2_4") (pintype "passive"))
      (node (ref "R4") (pin "1") (pinfunction "1_1") (pintype "passive"))
      (node (ref "X1") (pin "A7") (pinfunction "D-_A7") (pintype "bidirectional"))
      (node (ref "X1") (pin "B7") (pinfunction "D-_B7") (pintype "bidirectional"))
    )
    (net (code "24") (name "Net-(C11-Pad1)") (class "Default")
      (node (ref "C11") (pin "1") (pinfunction "1_1") (pintype "passive"))
      (node (ref "D3") (pin "1") (pinfunction "IO1_1") (pintype "passive"))
      (node (ref "D3") (pin "6") (pinfunction "IO1_6") (pintype "passive"))
      (node (ref "R5") (pin "1") (pinfunction "1_1") (pintype "passive"))
      (node (ref "X1") (pin "A6") (pinfunction "D+_A6") (pintype "bidirectional"))
      (node (ref "X1") (pin "B6") (pinfunction "D+_B6") (pintype "bidirectional"))
    )
    (net (code "25") (name "Net-(D1-PadC)") (class "Default")
      (node (ref "D1") (pin "C") (pinfunction "C_C") (pintype "passive"))
      (node (ref "R1") (pin "1") (pinfunction "1_1") (pintype "passive"))
    )
    (net (code "26") (name "Net-(D3-VCC)") (class "Default")
      (node (ref "D3") (pin "5") (pinfunction "VCC_5") (pintype "power_in"))
      (node (ref "F1") (pin "1") (pinfunction "2_1") (pintype "passive"))
      (node (ref "X1") (pin "A4_B9") (pinfunction "VBUS_A4_B9") (pintype "power_in"))
      (node (ref "X1") (pin "B4_A9") (pinfunction "VBUS_B4_A9") (pintype "power_in"))
      (node (ref "X9") (pin "2") (pinfunction "2_2") (pintype "bidirectional"))
    )
    (net (code "27") (name "Net-(D4-DIN)") (class "Default")
      (node (ref "D4") (pin "4") (pinfunction "DIN_4") (pintype "input"))
      (node (ref "Q6") (pin "3") (pinfunction "D_3") (pintype "passive"))
      (node (ref "RN6") (pin "7") (pinfunction "7_7") (pintype "passive"))
    )
    (net (code "28") (name "Net-(D6-PadA)") (class "Default")
      (node (ref "D6") (pin "A") (pinfunction "A_A") (pintype "passive"))
      (node (ref "R18") (pin "1") (pinfunction "1_1") (pintype "passive"))
    )
    (net (code "29") (name "Net-(IC1-AVIN)") (class "Default")
      (node (ref "C3") (pin "1") (pinfunction "1_1") (pintype "passive"))
      (node (ref "C6") (pin "1") (pinfunction "1_1") (pintype "passive"))
      (node (ref "D2") (pin "2") (pinfunction "VOUT_2") (pintype "power_in"))
      (node (ref "D2") (pin "7") (pinfunction "VOUT_7") (pintype "power_in"))
      (node (ref "IC1") (pin "A1") (pinfunction "PVIN_A1") (pintype "power_in"))
      (node (ref "IC1") (pin "B1") (pinfunction "PVIN_B1") (pintype "power_in"))
      (node (ref "IC1") (pin "C1") (pinfunction "PVIN_C1") (pintype "power_in"))
      (node (ref "IC1") (pin "D1") (pinfunction "AVIN_D1") (pintype "power_in"))
      (node (ref "IC1") (pin "D3") (pinfunction "MODE_D3") (pintype "input"))
      (node (ref "IC4") (pin "4") (pinfunction "SOURCE_4") (pintype "passive"))
      (node (ref "IC5") (pin "4") (pinfunction "SOURCE_4") (pintype "passive"))
      (node (ref "IC9") (pin "4") (pinfunction "4_4") (pintype "bidirectional"))
      (node (ref "Q1") (pin "1") (pinfunction "S_1") (pintype "passive"))
      (node (ref "Q1") (pin "4") (pinfunction "S_4") (pintype "passive"))
      (node (ref "SW1") (pin "6") (pinfunction "NC2_6") (pintype "passive"))
    )
    (net (code "30") (name "Net-(IC1-BOLX-PadA4)") (class "Default")
      (node (ref "IC1") (pin "A4") (pinfunction "BOLX_A4") (pintype "output"))
      (node (ref "IC1") (pin "B4") (pinfunction "BOLX_B4") (pintype "output"))
      (node (ref "IC1") (pin "C4") (pinfunction "BOLX_C4") (pintype "output"))
      (node (ref "L1") (pin "1") (pinfunction "1_1") (pintype "passive"))
    )
    (net (code "31") (name "Net-(IC1-BULX-PadA2)") (class "Default")
      (node (ref "IC1") (pin "A2") (pinfunction "BULX_A2") (pintype "output"))
      (node (ref "IC1") (pin "B2") (pinfunction "BULX_B2") (pintype "output"))
      (node (ref "IC1") (pin "C2") (pinfunction "BULX_C2") (pintype "output"))
      (node (ref "L1") (pin "2") (pinfunction "2_2") (pintype "passive"))
    )
    (net (code "32") (name "Net-(IC2-PROG)") (class "Default")
      (node (ref "IC2") (pin "5") (pinfunction "PROG_5") (pintype "input"))
      (node (ref "R2") (pin "2") (pinfunction "2_2") (pintype "passive"))
    )
    (net (code "33") (name "Net-(IC2-STAT)") (class "Default")
      (node (ref "IC2") (pin "1") (pinfunction "STAT_1") (pintype "open_collector"))
      (node (ref "R1") (pin "2") (pinfunction "2_2") (pintype "passive"))
    )
    (net (code "34") (name "Net-(IC3-IO15)") (class "Default")
      (node (ref "C14") (pin "1") (pinfunction "1_1") (pintype "passive"))
      (node (ref "IC3") (pin "19") (pinfunction "IO15_19") (pintype "bidirectional"))
      (node (ref "Q7") (pin "2") (pinfunction "2_2") (pintype "passive"))
      (node (ref "XT1") (pin "2") (pinfunction "2_2") (pintype "passive"))
    )
    (net (code "35") (name "Net-(IC3-IO16)") (class "Default")
      (node (ref "C15") (pin "2") (pinfunction "2_2") (pintype "passive"))
      (node (ref "IC3") (pin "20") (pinfunction "IO16_20") (pintype "bidirectional"))
      (node (ref "Q7") (pin "1") (pinfunction "1_1") (pintype "passive"))
      (node (ref "XT1") (pin "1") (pinfunction "1_1") (pintype "passive"))
    )
    (net (code "36") (name "Net-(IC4-RBIAS)") (class "Default")
      (node (ref "IC4") (pin "3") (pinfunction "RBIAS_3") (pintype "passive"))
      (node (ref "Q1") (pin "2") (pinfunction "G_2") (pintype "passive"))
      (node (ref "R8") (pin "2") (pinfunction "2_2") (pintype "passive"))
    )
    (net (code "37") (name "Net-(IC4-REF)") (class "Default")
      (node (ref "IC4") (pin "2") (pinfunction "REF_2") (pintype "input"))
      (node (ref "R10") (pin "2") (pinfunction "2_2") (pintype "passive"))
    )
    (net (code "38") (name "Net-(IC5-RBIAS)") (class "Default")
      (node (ref "IC5") (pin "3") (pinfunction "RBIAS_3") (pintype "passive"))
      (node (ref "Q1") (pin "5") (pinfunction "G_5") (pintype "passive"))
      (node (ref "R9") (pin "2") (pinfunction "2_2") (pintype "passive"))
    )
    (net (code "39") (name "Net-(IC5-REF)") (class "Default")
      (node (ref "IC5") (pin "2") (pinfunction "REF_2") (pintype "input"))
      (node (ref "R11") (pin "2") (pinfunction "2_2") (pintype "passive"))
    )
    (net (code "40") (name "Net-(IC7-REGOUT)") (class "Default")
      (node (ref "C24") (pin "2") (pinfunction "2_2") (pintype "passive"))
      (node (ref "IC7") (pin "10") (pinfunction "REGOUT_10") (pintype "power_in"))
    )
    (net (code "41") (name "Net-(Q2-D)") (class "Default")
      (node (ref "Q2") (pin "3") (pinfunction "D_3") (pintype "passive"))
      (node (ref "X12") (pin "4") (pinfunction "VCC_4") (pintype "power_in"))
    )
    (net (code "42") (name "Net-(Q3-D)") (class "Default")
      (node (ref "Q3") (pin "3") (pinfunction "D_3") (pintype "passive"))
      (node (ref "X10") (pin "1") (pinfunction "1_1") (pintype "passive"))
    )
    (net (code "43") (name "Net-(Q4-D)") (class "Default")
      (node (ref "Q4") (pin "3") (pinfunction "D_3") (pintype "passive"))
      (node (ref "X3") (pin "2") (pinfunction "2_2") (pintype "bidirectional"))
      (node (ref "X5") (pin "2") (pinfunction "2_2") (pintype "bidirectional"))
      (node (ref "X6") (pin "2") (pinfunction "2_2") (pintype "bidirectional"))
    )
    (net (code "44") (name "Net-(Q5-D)") (class "Default")
      (node (ref "Q5") (pin "3") (pinfunction "D_3") (pintype "passive"))
      (node (ref "R22") (pin "2") (pinfunction "2_2") (pintype "passive"))
      (node (ref "X4") (pin "2") (pinfunction "2_2") (pintype "bidirectional"))
    )
    (net (code "45") (name "Net-(Q5-G)") (class "Default")
      (node (ref "Q5") (pin "1") (pinfunction "G_1") (pintype "passive"))
      (node (ref "R16") (pin "2") (pinfunction "2_2") (pintype "passive"))
      (node (ref "R21") (pin "2") (pinfunction "2_2") (pintype "passive"))
    )
    (net (code "46") (name "Net-(Q6A-D)") (class "Default")
      (node (ref "D6") (pin "C") (pinfunction "C_C") (pintype "passive"))
      (node (ref "Q6") (pin "6") (pinfunction "D_6") (pintype "passive"))
    )
    (net (code "47") (name "Net-(RN1-Pad5)") (class "Default")
      (node (ref "RN1") (pin "5") (pinfunction "5_5") (pintype "passive"))
      (node (ref "X6") (pin "4") (pinfunction "4_4") (pintype "bidirectional"))
    )
    (net (code "48") (name "Net-(RN1-Pad6)") (class "Default")
      (node (ref "RN1") (pin "6") (pinfunction "6_6") (pintype "passive"))
      (node (ref "X6") (pin "3") (pinfunction "3_3") (pintype "bidirectional"))
    )
    (net (code "49") (name "Net-(RN1-Pad7)") (class "Default")
      (node (ref "RN1") (pin "7") (pinfunction "7_7") (pintype "passive"))
      (node (ref "X5") (pin "4") (pinfunction "4_4") (pintype "bidirectional"))
    )
    (net (code "50") (name "Net-(RN1-Pad8)") (class "Default")
      (node (ref "RN1") (pin "8") (pinfunction "8_8") (pintype "passive"))
      (node (ref "X5") (pin "3") (pinfunction "3_3") (pintype "bidirectional"))
    )
    (net (code "51") (name "Net-(RN3-Pad5)") (class "Default")
      (node (ref "RN3") (pin "5") (pinfunction "5_5") (pintype "passive"))
      (node (ref "X3") (pin "4") (pinfunction "4_4") (pintype "bidirectional"))
    )
    (net (code "52") (name "Net-(RN3-Pad6)") (class "Default")
      (node (ref "RN3") (pin "6") (pinfunction "6_6") (pintype "passive"))
      (node (ref "X3") (pin "3") (pinfunction "3_3") (pintype "bidirectional"))
    )
    (net (code "53") (name "Net-(RN3-Pad7)") (class "Default")
      (node (ref "RN3") (pin "7") (pinfunction "7_7") (pintype "passive"))
      (node (ref "X4") (pin "4") (pinfunction "4_4") (pintype "bidirectional"))
    )
    (net (code "54") (name "Net-(RN3-Pad8)") (class "Default")
      (node (ref "RN3") (pin "8") (pinfunction "8_8") (pintype "passive"))
      (node (ref "X4") (pin "3") (pinfunction "3_3") (pintype "bidirectional"))
    )
    (net (code "55") (name "Net-(RN4-Pad5)") (class "Default")
      (node (ref "RN4") (pin "5") (pinfunction "5_5") (pintype "passive"))
      (node (ref "RN5") (pin "5") (pinfunction "5_5") (pintype "passive"))
      (node (ref "RN5") (pin "6") (pinfunction "6_6") (pintype "passive"))
      (node (ref "X7") (pin "3") (pinfunction "3_3") (pintype "bidirectional"))
      (node (ref "X8") (pin "3") (pinfunction "3_3") (pintype "bidirectional"))
    )
    (net (code "56") (name "Net-(RN4-Pad6)") (class "Default")
      (node (ref "RN4") (pin "6") (pinfunction "6_6") (pintype "passive"))
      (node (ref "RN5") (pin "7") (pinfunction "7_7") (pintype "passive"))
      (node (ref "RN5") (pin "8") (pinfunction "8_8") (pintype "passive"))
      (node (ref "X7") (pin "4") (pinfunction "4_4") (pintype "bidirectional"))
      (node (ref "X8") (pin "4") (pinfunction "4_4") (pintype "bidirectional"))
    )
    (net (code "57") (name "Net-(X1-CC1)") (class "Default")
      (node (ref "R7") (pin "2") (pinfunction "2_2") (pintype "passive"))
      (node (ref "X1") (pin "A5") (pinfunction "CC1_A5") (pintype "passive"))
    )
    (net (code "58") (name "Net-(X1-CC2)") (class "Default")
      (node (ref "R6") (pin "2") (pinfunction "2_2") (pintype "passive"))
      (node (ref "X1") (pin "B5") (pinfunction "CC2_B5") (pintype "passive"))
    )
    (net (code "59") (name "PD_ENABLE") (class "Default")
      (node (ref "D5") (pin "A") (pinfunction "A_A") (pintype "passive"))
      (node (ref "IC3") (pin "25") (pinfunction "IO21_25") (pintype "bidirectional"))
    )
    (net (code "60") (name "PD_SENSE") (class "Default")
      (node (ref "D5") (pin "C") (pinfunction "C_C") (pintype "passive"))
      (node (ref "IC3") (pin "18") (pinfunction "IO14_18") (pintype "bidirectional"))
      (node (ref "R17") (pin "2") (pinfunction "2_2") (pintype "passive"))
    )
    (net (code "61") (name "QWIIC_SCL") (class "Default")
      (node (ref "IC3") (pin "36") (pinfunction "IO40_36") (pintype "bidirectional"))
      (node (ref "RN4") (pin "3") (pinfunction "3_3") (pintype "passive"))
    )
    (net (code "62") (name "QWIIC_SDA") (class "Default")
      (node (ref "IC3") (pin "35") (pinfunction "IO39_35") (pintype "bidirectional"))
      (node (ref "RN4") (pin "4") (pinfunction "4_4") (pintype "passive"))
    )
    (net (code "63") (name "SD_CS") (class "Default")
      (node (ref "IC3") (pin "14") (pinfunction "IO10_14") (pintype "bidirectional"))
      (node (ref "X12") (pin "2") (pinfunction "CD/DAT3_2") (pintype "bidirectional"))
    )
    (net (code "64") (name "SD_ENABLE") (class "Default")
      (node (ref "IC3") (pin "13") (pinfunction "IO9_13") (pintype "bidirectional"))
      (node (ref "Q2") (pin "1") (pinfunction "G_1") (pintype "passive"))
    )
    (net (code "65") (name "SD_MISO") (class "Default")
      (node (ref "IC3") (pin "17") (pinfunction "IO13_17") (pintype "bidirectional"))
      (node (ref "R13") (pin "2") (pinfunction "2_2") (pintype "passive"))
      (node (ref "X12") (pin "7") (pinfunction "DAT0_7") (pintype "bidirectional"))
    )
    (net (code "66") (name "SD_MOSI") (class "Default")
      (node (ref "IC3") (pin "15") (pinfunction "IO11_15") (pintype "bidirectional"))
      (node (ref "X12") (pin "3") (pinfunction "CMD_3") (pintype "input"))
    )
    (net (code "67") (name "SD_SCLK") (class "Default")
      (node (ref "IC3") (pin "16") (pinfunction "IO12_16") (pintype "bidirectional"))
      (node (ref "X12") (pin "5") (pinfunction "CLK_5") (pintype "input"))
    )
    (net (code "68") (name "UART_ENABLE") (class "Default")
      (node (ref "IC3") (pin "26") (pinfunction "IO26_26") (pintype "bidirectional"))
      (node (ref "R21") (pin "1") (pinfunction "1_1") (pintype "passive"))
    )
    (net (code "69") (name "UART_RXD") (class "Default")
      (node (ref "IC3") (pin "40") (pinfunction "RXD0_40") (pintype "bidirectional"))
      (node (ref "RN3") (pin "1") (pinfunction "1_1") (pintype "passive"))
    )
    (net (code "70") (name "UART_TXD") (class "Default")
      (node (ref "IC3") (pin "39") (pinfunction "TXD0_39") (pintype "bidirectional"))
      (node (ref "RN3") (pin "2") (pinfunction "2_2") (pintype "passive"))
    )
    (net (code "71") (name "USB_D+") (class "Default")
      (node (ref "IC3") (pin "24") (pinfunction "IO20_24") (pintype "bidirectional"))
      (node (ref "R5") (pin "2") (pinfunction "2_2") (pintype "passive"))
    )
    (net (code "72") (name "USB_D-") (class "Default")
      (node (ref "IC3") (pin "23") (pinfunction "IO19_23") (pintype "bidirectional"))
      (node (ref "R4") (pin "2") (pinfunction "2_2") (pintype "passive"))
    )
    (net (code "73") (name "VBAT") (class "Default")
      (node (ref "C13") (pin "1") (pinfunction "1_1") (pintype "passive"))
      (node (ref "C4") (pin "1") (pinfunction "1_1") (pintype "passive"))
      (node (ref "D2") (pin "6") (pinfunction "VIN2_6") (pintype "power_in"))
      (node (ref "IC2") (pin "3") (pinfunction "VBAT_3") (pintype "bidirectional"))
      (node (ref "IC4") (pin "6") (pinfunction "DRAIN_6") (pintype "passive"))
      (node (ref "Q1") (pin "6") (pinfunction "D_6") (pintype "passive"))
      (node (ref "Q1") (pin "7") (pinfunction "D_7") (pintype "passive"))
      (node (ref "X2") (pin "1") (pinfunction "1_1") (pintype "bidirectional"))
    )
    (net (code "74") (name "VCC_LED") (class "Default")
      (node (ref "C16") (pin "2") (pinfunction "2_2") (pintype "passive"))
      (node (ref "D4") (pin "1") (pinfunction "VCC_1") (pintype "power_in"))
      (node (ref "R12") (pin "1") (pinfunction "1_1") (pintype "passive"))
      (node (ref "RN6") (pin "2") (pinfunction "2_2") (pintype "passive"))
      (node (ref "RN6") (pin "3") (pinfunction "3_3") (pintype "passive"))
      (node (ref "RN6") (pin "4") (pinfunction "4_4") (pintype "passive"))
      (node (ref "SW1") (pin "5") (pinfunction "C2_5") (pintype "passive"))
    )
    (net (code "75") (name "VUSB") (class "Default")
      (node (ref "C5") (pin "1") (pinfunction "1_1") (pintype "passive"))
      (node (ref "D1") (pin "A") (pinfunction "A_A") (pintype "passive"))
      (node (ref "F1") (pin "2") (pinfunction "3_2") (pintype "passive"))
      (node (ref "IC2") (pin "4") (pinfunction "VIN_4") (pintype "power_in"))
      (node (ref "IC5") (pin "6") (pinfunction "DRAIN_6") (pintype "passive"))
      (node (ref "IC9") (pin "2") (pinfunction "2_2") (pintype "bidirectional"))
      (node (ref "Q1") (pin "3") (pinfunction "D_3") (pintype "passive"))
      (node (ref "Q1") (pin "8") (pinfunction "D_8") (pintype "passive"))
      (node (ref "R18") (pin "2") (pinfunction "2_2") (pintype "passive"))
      (node (ref "SW1") (pin "2") (pinfunction "C1_2") (pintype "passive"))
    )
    (net (code "76") (name "XBEE_CS") (class "Default")
      (node (ref "IC3") (pin "29") (pinfunction "IO34_29") (pintype "bidirectional"))
      (node (ref "X11") (pin "7") (pinfunction "7_7") (pintype "passive"))
    )
    (net (code "77") (name "XBEE_ENABLE") (class "Default")
      (node (ref "IC3") (pin "37") (pinfunction "IO41_37") (pintype "bidirectional"))
      (node (ref "Q3") (pin "1") (pinfunction "G_1") (pintype "passive"))
      (node (ref "R14") (pin "2") (pinfunction "2_2") (pintype "passive"))
    )
    (net (code "78") (name "XBEE_INT") (class "Default")
      (node (ref "IC3") (pin "28") (pinfunction "IO33_28") (pintype "bidirectional"))
      (node (ref "X11") (pin "2") (pinfunction "2_2") (pintype "passive"))
    )
    (net (code "79") (name "XBEE_MISO") (class "Default")
      (node (ref "IC3") (pin "33") (pinfunction "IO37_33") (pintype "bidirectional"))
      (node (ref "X10") (pin "4") (pinfunction "4_4") (pintype "passive"))
    )
    (net (code "80") (name "XBEE_MOSI") (class "Default")
      (node (ref "IC3") (pin "31") (pinfunction "IO35_31") (pintype "bidirectional"))
      (node (ref "X11") (pin "1") (pinfunction "1_1") (pintype "passive"))
    )
    (net (code "81") (name "XBEE_RESET") (class "Default")
      (node (ref "IC3") (pin "34") (pinfunction "IO38_34") (pintype "bidirectional"))
      (node (ref "X10") (pin "5") (pinfunction "5_5") (pintype "passive"))
    )
    (net (code "82") (name "XBEE_RXD") (class "Default")
      (node (ref "IC3") (pin "22") (pinfunction "IO18_22") (pintype "bidirectional"))
      (node (ref "X10") (pin "2") (pinfunction "2_2") (pintype "passive"))
    )
    (net (code "83") (name "XBEE_SCLK") (class "Default")
      (node (ref "IC3") (pin "32") (pinfunction "IO36_32") (pintype "bidirectional"))
      (node (ref "X11") (pin "8") (pinfunction "8_8") (pintype "passive"))
    )
    (net (code "84") (name "XBEE_TXD") (class "Default")
      (node (ref "IC3") (pin "21") (pinfunction "IO17_21") (pintype "bidirectional"))
      (node (ref "X10") (pin "3") (pinfunction "3_3") (pintype "passive"))
    )
    (net (code "85") (name "unconnected-(D2-ST-Pad8)") (class "Default")
      (node (ref "D2") (pin "8") (pinfunction "ST_8") (pintype "open_collector"))
    )
    (net (code "86") (name "unconnected-(D4-DOUT-Pad2)") (class "Default")
      (node (ref "D4") (pin "2") (pinfunction "DOUT_2") (pintype "output"))
    )
    (net (code "87") (name "unconnected-(IC7-AUX_CL-Pad7)") (class "Default")
      (node (ref "IC7") (pin "7") (pinfunction "AUX_CL_7") (pintype "output"))
    )
    (net (code "88") (name "unconnected-(IC7-AUX_DA-Pad21)") (class "Default")
      (node (ref "IC7") (pin "21") (pinfunction "AUX_DA_21") (pintype "bidirectional"))
    )
    (net (code "89") (name "unconnected-(RN4-Pad1)") (class "Default")
      (node (ref "RN4") (pin "1") (pinfunction "1_1") (pintype "passive"))
    )
    (net (code "90") (name "unconnected-(RN4-Pad2)") (class "Default")
      (node (ref "RN4") (pin "2") (pinfunction "2_2") (pintype "passive"))
    )
    (net (code "91") (name "unconnected-(RN4-Pad7)") (class "Default")
      (node (ref "RN4") (pin "7") (pinfunction "7_7") (pintype "passive"))
    )
    (net (code "92") (name "unconnected-(RN4-Pad8)") (class "Default")
      (node (ref "RN4") (pin "8") (pinfunction "8_8") (pintype "passive"))
    )
    (net (code "93") (name "unconnected-(RN6-Pad5)") (class "Default")
      (node (ref "RN6") (pin "5") (pinfunction "5_5") (pintype "passive"))
    )
    (net (code "94") (name "unconnected-(RN6-Pad6)") (class "Default")
      (node (ref "RN6") (pin "6") (pinfunction "6_6") (pintype "passive"))
    )
    (net (code "95") (name "unconnected-(SW1-NO1-Pad1)") (class "Default")
      (node (ref "SW1") (pin "1") (pinfunction "NO1_1") (pintype "passive"))
    )
    (net (code "96") (name "unconnected-(X10-Pad6)") (class "Default")
      (node (ref "X10") (pin "6") (pinfunction "6_6") (pintype "passive"))
    )
    (net (code "97") (name "unconnected-(X10-Pad7)") (class "Default")
      (node (ref "X10") (pin "7") (pinfunction "7_7") (pintype "passive"))
    )
    (net (code "98") (name "unconnected-(X10-Pad8)") (class "Default")
      (node (ref "X10") (pin "8") (pinfunction "8_8") (pintype "passive"))
    )
    (net (code "99") (name "unconnected-(X10-Pad9)") (class "Default")
      (node (ref "X10") (pin "9") (pinfunction "9_9") (pintype "passive"))
    )
    (net (code "100") (name "unconnected-(X11-Pad3)") (class "Default")
      (node (ref "X11") (pin "3") (pinfunction "3_3") (pintype "passive"))
    )
    (net (code "101") (name "unconnected-(X11-Pad4)") (class "Default")
      (node (ref "X11") (pin "4") (pinfunction "4_4") (pintype "passive"))
    )
    (net (code "102") (name "unconnected-(X11-Pad5)") (class "Default")
      (node (ref "X11") (pin "5") (pinfunction "5_5") (pintype "passive"))
    )
    (net (code "103") (name "unconnected-(X11-Pad6)") (class "Default")
      (node (ref "X11") (pin "6") (pinfunction "6_6") (pintype "passive"))
    )
    (net (code "104") (name "unconnected-(X11-Pad9)") (class "Default")
      (node (ref "X11") (pin "9") (pinfunction "9_9") (pintype "passive"))
    )
    (net (code "105") (name "unconnected-(X11-Pad10)") (class "Default")
      (node (ref "X11") (pin "10") (pinfunction "10_10") (pintype "passive"))
    )
    (net (code "106") (name "unconnected-(X12-CD-Pad9)") (class "Default")
      (node (ref "X12") (pin "9") (pinfunction "CD_9") (pintype "passive"))
    )
    (net (code "107") (name "unconnected-(X12-DAT1-Pad8)") (class "Default")
      (node (ref "X12") (pin "8") (pinfunction "DAT1_8") (pintype "bidirectional"))
    )
    (net (code "108") (name "unconnected-(X12-DAT2-Pad1)") (class "Default")
      (node (ref "X12") (pin "1") (pinfunction "DAT2_1") (pintype "bidirectional"))
    )
  )
)
